# Elekid_03.net
KiCad netlist of a schematic drawn in Altium Designer
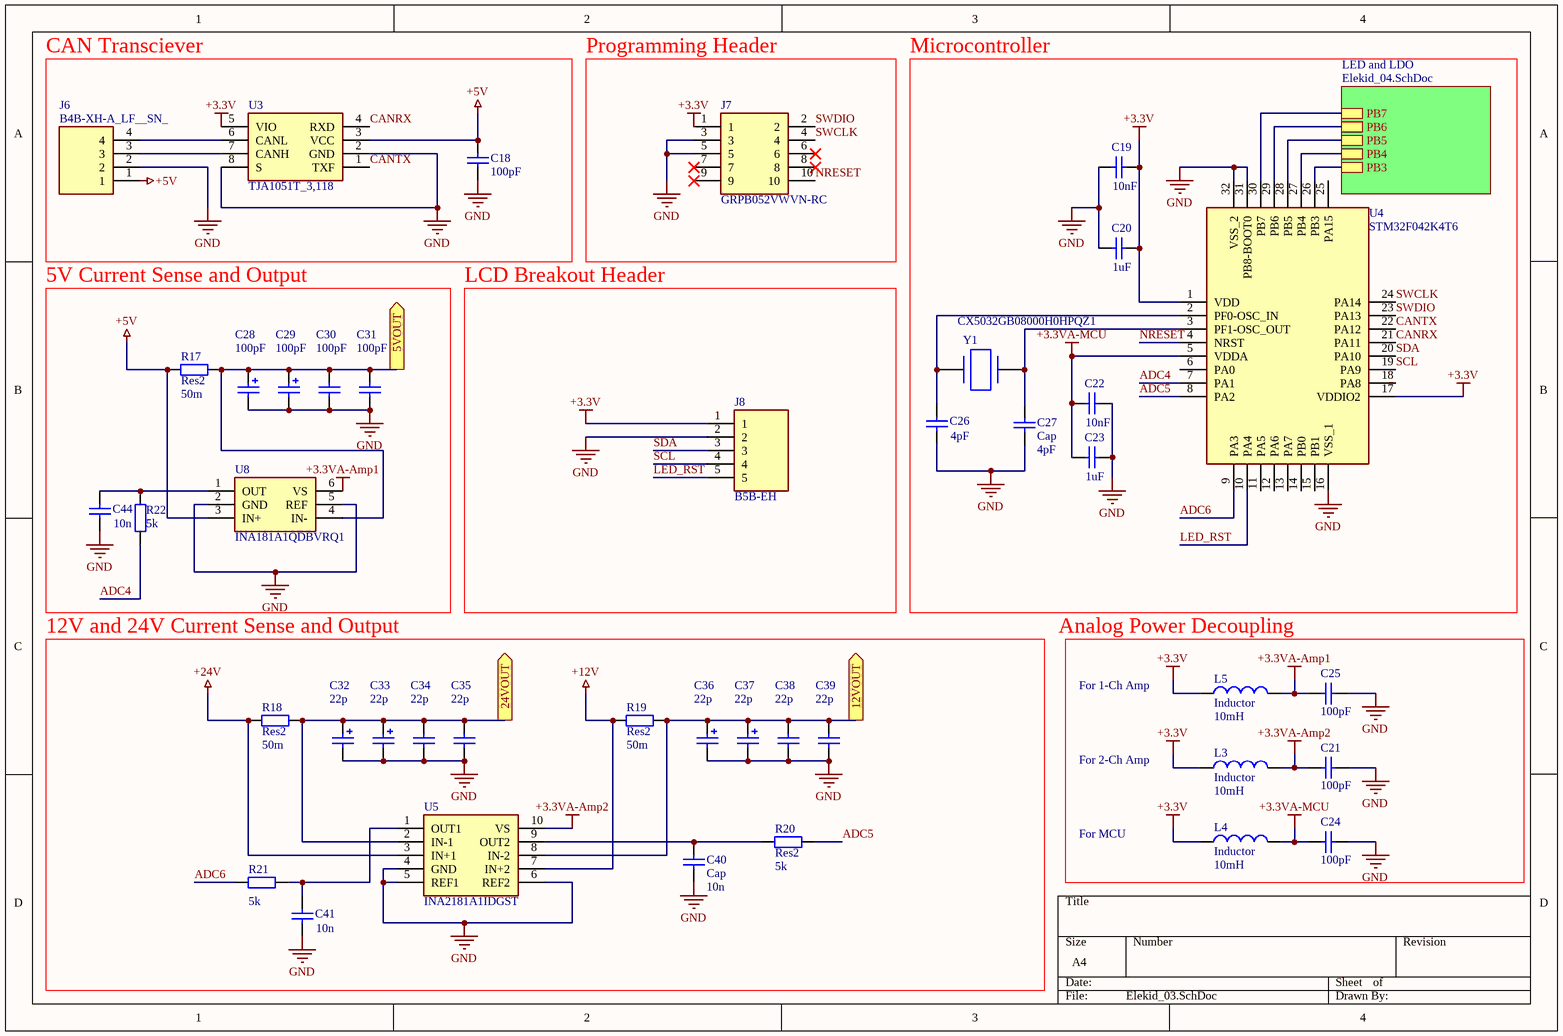
[diagram p0: Elekid_03.SchDoc]

(export (version "E")
  (design (tool "Eeschema 10.0.6"))
  (components
    (comp (ref "C18")
      (value "100pF")
      (footprint "C0805")
      (description "Capacitor")
      (fields (field (name "Comment") "Cap") (field (name "PUBLISHER") "Altium Limited"))
      (libsource (lib "Miscellaneous Devices") (part "Cap"))
    )
    (comp (ref "C19")
      (value "10nF")
      (footprint "C0805")
      (description "Capacitor")
      (fields (field (name "Comment") "Cap") (field (name "PUBLISHER") "Altium Limited"))
      (libsource (lib "Miscellaneous Devices") (part "Cap"))
    )
    (comp (ref "C20")
      (value "1uF")
      (footprint "C0805")
      (description "Capacitor")
      (fields (field (name "Comment") "Cap") (field (name "PUBLISHER") "Altium Limited"))
      (libsource (lib "Miscellaneous Devices") (part "Cap"))
    )
    (comp (ref "C21")
      (value "100pF")
      (footprint "C0805")
      (description "Capacitor")
      (fields (field (name "Comment") "Cap") (field (name "PUBLISHER") "Altium Limited"))
      (libsource (lib "Miscellaneous Devices") (part "Cap"))
    )
    (comp (ref "C22")
      (value "10nF")
      (footprint "C0805")
      (description "Capacitor")
      (fields (field (name "Comment") "Cap") (field (name "PUBLISHER") "Altium Limited"))
      (libsource (lib "Miscellaneous Devices") (part "Cap"))
    )
    (comp (ref "C23")
      (value "1uF")
      (footprint "C0805")
      (description "Capacitor")
      (fields (field (name "Comment") "Cap") (field (name "PUBLISHER") "Altium Limited"))
      (libsource (lib "Miscellaneous Devices") (part "Cap"))
    )
    (comp (ref "C24")
      (value "100pF")
      (footprint "C0805")
      (description "Capacitor")
      (fields (field (name "Comment") "Cap") (field (name "PUBLISHER") "Altium Limited"))
      (libsource (lib "Miscellaneous Devices") (part "Cap"))
    )
    (comp (ref "C25")
      (value "100pF")
      (footprint "C0805")
      (description "Capacitor")
      (fields (field (name "Comment") "Cap") (field (name "PUBLISHER") "Altium Limited"))
      (libsource (lib "Miscellaneous Devices") (part "Cap"))
    )
    (comp (ref "C26")
      (value "4pF")
      (footprint "C0805")
      (description "Capacitor")
      (fields (field (name "Comment") "Cap") (field (name "PUBLISHER") "Altium Limited"))
      (libsource (lib "Miscellaneous Devices") (part "Cap"))
    )
    (comp (ref "C27")
      (value "Cap")
      (footprint "C0805")
      (description "Capacitor")
      (fields (field (name "ALTIUM_VALUE") "4pF") (field (name "PUBLISHER") "Altium Limited"))
      (libsource (lib "Miscellaneous Devices") (part "Cap"))
    )
    (comp (ref "C28")
      (value "100pF")
      (footprint "C0805")
      (description "Polarized Capacitor (Axial)")
      (fields (field (name "Comment") "Cap Pol2") (field (name "PUBLISHER") "Altium Limited"))
      (libsource (lib "Miscellaneous Devices") (part "Cap Pol2"))
    )
    (comp (ref "C29")
      (value "100pF")
      (footprint "C0805")
      (description "Polarized Capacitor (Axial)")
      (fields (field (name "Comment") "Cap Pol2") (field (name "PUBLISHER") "Altium Limited"))
      (libsource (lib "Miscellaneous Devices") (part "Cap Pol2"))
    )
    (comp (ref "C30")
      (value "100pF")
      (footprint "C0805")
      (description "Capacitor")
      (fields (field (name "Comment") "Cap") (field (name "PUBLISHER") "Altium Limited"))
      (libsource (lib "Miscellaneous Devices") (part "Cap"))
    )
    (comp (ref "C31")
      (value "100pF")
      (footprint "C0805")
      (description "Capacitor")
      (fields (field (name "Comment") "Cap") (field (name "PUBLISHER") "Altium Limited"))
      (libsource (lib "Miscellaneous Devices") (part "Cap"))
    )
    (comp (ref "C32")
      (value "22p")
      (footprint "C0805")
      (description "Polarized Capacitor (Axial)")
      (fields (field (name "Comment") "Cap Pol2") (field (name "PUBLISHER") "Altium Limited"))
      (libsource (lib "Miscellaneous Devices") (part "Cap Pol2"))
    )
    (comp (ref "C33")
      (value "22p")
      (footprint "C0805")
      (description "Polarized Capacitor (Axial)")
      (fields (field (name "Comment") "Cap Pol2") (field (name "PUBLISHER") "Altium Limited"))
      (libsource (lib "Miscellaneous Devices") (part "Cap Pol2"))
    )
    (comp (ref "C34")
      (value "22p")
      (footprint "C0805")
      (description "Capacitor")
      (fields (field (name "Comment") "Cap") (field (name "PUBLISHER") "Altium Limited"))
      (libsource (lib "Miscellaneous Devices") (part "Cap"))
    )
    (comp (ref "C35")
      (value "22p")
      (footprint "C0805")
      (description "Capacitor")
      (fields (field (name "Comment") "Cap") (field (name "PUBLISHER") "Altium Limited"))
      (libsource (lib "Miscellaneous Devices") (part "Cap"))
    )
    (comp (ref "C36")
      (value "22p")
      (footprint "C0805")
      (description "Polarized Capacitor (Axial)")
      (fields (field (name "Comment") "Cap Pol2") (field (name "PUBLISHER") "Altium Limited"))
      (libsource (lib "Miscellaneous Devices") (part "Cap Pol2"))
    )
    (comp (ref "C37")
      (value "22p")
      (footprint "C0805")
      (description "Polarized Capacitor (Axial)")
      (fields (field (name "Comment") "Cap Pol2") (field (name "PUBLISHER") "Altium Limited"))
      (libsource (lib "Miscellaneous Devices") (part "Cap Pol2"))
    )
    (comp (ref "C38")
      (value "22p")
      (footprint "C0805")
      (description "Capacitor")
      (fields (field (name "Comment") "Cap") (field (name "PUBLISHER") "Altium Limited"))
      (libsource (lib "Miscellaneous Devices") (part "Cap"))
    )
    (comp (ref "C39")
      (value "22p")
      (footprint "C0805")
      (description "Capacitor")
      (fields (field (name "Comment") "Cap") (field (name "PUBLISHER") "Altium Limited"))
      (libsource (lib "Miscellaneous Devices") (part "Cap"))
    )
    (comp (ref "C40")
      (value "Cap")
      (footprint "C0805")
      (description "Capacitor")
      (fields (field (name "ALTIUM_VALUE") "10n") (field (name "PUBLISHER") "Altium Limited"))
      (libsource (lib "Miscellaneous Devices") (part "Cap"))
    )
    (comp (ref "C41")
      (value "10n")
      (footprint "C0805")
      (description "Capacitor")
      (fields (field (name "Comment") "Cap") (field (name "PUBLISHER") "Altium Limited"))
      (libsource (lib "Miscellaneous Devices") (part "Cap"))
    )
    (comp (ref "C44")
      (value "10n")
      (footprint "C0805")
      (description "Capacitor")
      (fields (field (name "Comment") "Cap") (field (name "PUBLISHER") "Altium Limited"))
      (libsource (lib "Miscellaneous Devices") (part "Cap"))
    )
    (comp (ref "J6")
      (value "B4B-XH-A_LF__SN_")
      (footprint "Embedded:B4BXHALFSN")
      (description "Connector")
      (fields (field (name "MANUFACTURER_PART_NUMBER") "B4B-XH-A(LF)(SN)"))
      (libsource (lib "*") (part "B4B-XH-A_LF__SN_"))
    )
    (comp (ref "J7")
      (value "GRPB052VWVN-RC")
      (footprint "Embedded:HDRV10W50P127_2X5_635X340X430P")
      (description "Connector")
      (libsource (lib "Embedded") (part "GRPB052VWVN-RC"))
    )
    (comp (ref "J8")
      (value "B5B-EH")
      (footprint "Embedded:SHDR5W64P0X250_1X5_1500X380X600P")
      (description "Connector")
      (libsource (lib "*") (part "B5B-EH"))
    )
    (comp (ref "L3")
      (value "Inductor")
      (footprint "c0805")
      (fields (field (name "ALTIUM_VALUE") "10mH") (field (name "PUBLISHER") "Altium Limited"))
      (libsource (lib "Miscellaneous Devices") (part "Inductor"))
    )
    (comp (ref "L4")
      (value "Inductor")
      (footprint "c0805")
      (fields (field (name "ALTIUM_VALUE") "10mH") (field (name "PUBLISHER") "Altium Limited"))
      (libsource (lib "Miscellaneous Devices") (part "Inductor"))
    )
    (comp (ref "L5")
      (value "Inductor")
      (footprint "c0805")
      (fields (field (name "ALTIUM_VALUE") "10mH") (field (name "PUBLISHER") "Altium Limited"))
      (libsource (lib "Miscellaneous Devices") (part "Inductor"))
    )
    (comp (ref "R17")
      (value "Res2")
      (footprint "C1206")
      (description "Resistor")
      (fields (field (name "ALTIUM_VALUE") "50m") (field (name "PUBLISHER") "Altium Limited"))
      (libsource (lib "Miscellaneous Devices") (part "Res2"))
    )
    (comp (ref "R18")
      (value "Res2")
      (footprint "C1206")
      (description "Resistor")
      (fields (field (name "ALTIUM_VALUE") "50m") (field (name "PUBLISHER") "Altium Limited"))
      (libsource (lib "Miscellaneous Devices") (part "Res2"))
    )
    (comp (ref "R19")
      (value "Res2")
      (footprint "C1206")
      (description "Resistor")
      (fields (field (name "ALTIUM_VALUE") "50m") (field (name "PUBLISHER") "Altium Limited"))
      (libsource (lib "Miscellaneous Devices") (part "Res2"))
    )
    (comp (ref "R20")
      (value "Res2")
      (footprint "C0805")
      (description "Resistor")
      (fields (field (name "ALTIUM_VALUE") "5k") (field (name "PUBLISHER") "Altium Limited"))
      (libsource (lib "Miscellaneous Devices") (part "Res2"))
    )
    (comp (ref "R21")
      (value "5k")
      (footprint "C0805")
      (description "Resistor")
      (fields (field (name "Comment") "Res2") (field (name "PUBLISHER") "Altium Limited"))
      (libsource (lib "Miscellaneous Devices") (part "Res2"))
    )
    (comp (ref "R22")
      (value "5k")
      (footprint "C0805")
      (description "Resistor")
      (fields (field (name "Comment") "Res2") (field (name "PUBLISHER") "Altium Limited"))
      (libsource (lib "") (part "Res2_1"))
    )
    (comp (ref "U3")
      (value "TJA1051T_3,118")
      (footprint "Embedded:SOIC127P600X175-8N")
      (description "Integrated Circuit")
      (fields
        (field (name "MANUFACTURER_PART_NUMBER") "TJA1051T/3,118")
        (field (name "MOUSER PART NUMBER") "771-TJA1051T3118")
      )
      (libsource (lib "Embedded") (part "TJA1051T_3,118"))
    )
    (comp (ref "U4")
      (value "STM32F042K4T6")
      (footprint "Embedded:QFP80P900X900X160-32N")
      (description "Integrated Circuit")
      (fields (field (name "MOUSER PART NUMBER") "511-STM32F042K4T6"))
      (libsource (lib "*") (part "STM32F042K4T6"))
    )
    (comp (ref "U5")
      (value "INA2181A1IDGST")
      (footprint "Embedded:SOP50P490X110-10N")
      (description "Integrated Circuit")
      (fields
        (field (name "MANUFACTURER_PART_NUMBER") "INA2181A4IDGST")
        (field (name "MOUSER PART NUMBER") "595-INA2181A4IDGST")
      )
      (libsource (lib "*") (part "INA2181A4IDGST"))
    )
    (comp (ref "U8")
      (value "INA181A1QDBVRQ1")
      (footprint "Embedded:SOT95P280X145-6N")
      (description "Integrated Circuit")
      (fields (field (name "MOUSER PART NUMBER") "595-INA181A1QDBVRQ1"))
      (libsource (lib "*") (part "INA181A1QDBVRQ1"))
    )
    (comp (ref "Y1")
      (value "CX5032GB08000H0HPQZ1")
      (footprint "Embedded:CX5032GB08000H0HPQZ1")
      (description "Crystal or Oscillator")
      (fields (field (name "MOUSER PART NUMBER") "581-CX532GB8HHPQZ1"))
      (libsource (lib "*") (part "CX5032GB08000H0HPQZ1"))
    )
  )
  (nets
    (net (code "1") (name "+3.3V") (class "Default")
      (node (ref "C19") (pin "1") (pinfunction "1_1") (pintype "passive"))
      (node (ref "C20") (pin "1") (pinfunction "1_1") (pintype "passive"))
      (node (ref "J7") (pin "1") (pinfunction "1_1") (pintype "passive"))
      (node (ref "J8") (pin "1") (pinfunction "1_1") (pintype "passive"))
      (node (ref "L3") (pin "1") (pinfunction "1_1") (pintype "passive"))
      (node (ref "L4") (pin "1") (pinfunction "1_1") (pintype "passive"))
      (node (ref "L5") (pin "1") (pinfunction "1_1") (pintype "passive"))
      (node (ref "U3") (pin "5") (pinfunction "VIO_5") (pintype "passive"))
      (node (ref "U4") (pin "1") (pinfunction "VDD_1") (pintype "passive"))
      (node (ref "U4") (pin "17") (pinfunction "VDDIO2_17") (pintype "passive"))
    )
    (net (code "2") (name "+3.3VA-Amp1") (class "Default")
      (node (ref "C25") (pin "1") (pinfunction "1_1") (pintype "passive"))
      (node (ref "L5") (pin "2") (pinfunction "2_2") (pintype "passive"))
      (node (ref "U8") (pin "6") (pinfunction "VS_6") (pintype "passive"))
    )
    (net (code "3") (name "+3.3VA-Amp2") (class "Default")
      (node (ref "C21") (pin "1") (pinfunction "1_1") (pintype "passive"))
      (node (ref "L3") (pin "2") (pinfunction "2_2") (pintype "passive"))
      (node (ref "U5") (pin "10") (pinfunction "VS_10") (pintype "passive"))
    )
    (net (code "4") (name "+3.3VA-MCU") (class "Default")
      (node (ref "C22") (pin "2") (pinfunction "2_2") (pintype "passive"))
      (node (ref "C23") (pin "2") (pinfunction "2_2") (pintype "passive"))
      (node (ref "C24") (pin "1") (pinfunction "1_1") (pintype "passive"))
      (node (ref "L4") (pin "2") (pinfunction "2_2") (pintype "passive"))
      (node (ref "U4") (pin "5") (pinfunction "VDDA_5") (pintype "passive"))
    )
    (net (code "5") (name "+5V") (class "Default")
      (node (ref "C18") (pin "2") (pinfunction "2_2") (pintype "passive"))
      (node (ref "J6") (pin "1") (pinfunction "1_1") (pintype "passive"))
      (node (ref "R17") (pin "1") (pinfunction "1_1") (pintype "passive"))
      (node (ref "U3") (pin "3") (pinfunction "VCC_3") (pintype "passive"))
      (node (ref "U8") (pin "3") (pinfunction "IN+_3") (pintype "passive"))
    )
    (net (code "6") (name "+12V") (class "Default")
      (node (ref "R19") (pin "1") (pinfunction "1_1") (pintype "passive"))
      (node (ref "U5") (pin "7") (pinfunction "IN+2_7") (pintype "passive"))
    )
    (net (code "7") (name "+24V") (class "Default")
      (node (ref "R18") (pin "1") (pinfunction "1_1") (pintype "passive"))
      (node (ref "U5") (pin "3") (pinfunction "IN+1_3") (pintype "passive"))
    )
    (net (code "8") (name "/5VOUT") (class "Default")
      (node (ref "C28") (pin "1") (pinfunction "1_1") (pintype "passive"))
      (node (ref "C29") (pin "1") (pinfunction "1_1") (pintype "passive"))
      (node (ref "C30") (pin "2") (pinfunction "2_2") (pintype "passive"))
      (node (ref "C31") (pin "2") (pinfunction "2_2") (pintype "passive"))
      (node (ref "R17") (pin "2") (pinfunction "2_2") (pintype "passive"))
      (node (ref "U8") (pin "4") (pinfunction "IN-_4") (pintype "passive"))
    )
    (net (code "9") (name "/12VOUT") (class "Default")
      (node (ref "C36") (pin "1") (pinfunction "1_1") (pintype "passive"))
      (node (ref "C37") (pin "1") (pinfunction "1_1") (pintype "passive"))
      (node (ref "C38") (pin "2") (pinfunction "2_2") (pintype "passive"))
      (node (ref "C39") (pin "2") (pinfunction "2_2") (pintype "passive"))
      (node (ref "R19") (pin "2") (pinfunction "2_2") (pintype "passive"))
      (node (ref "U5") (pin "8") (pinfunction "IN-2_8") (pintype "passive"))
    )
    (net (code "10") (name "/24VOUT") (class "Default")
      (node (ref "C32") (pin "1") (pinfunction "1_1") (pintype "passive"))
      (node (ref "C33") (pin "1") (pinfunction "1_1") (pintype "passive"))
      (node (ref "C34") (pin "2") (pinfunction "2_2") (pintype "passive"))
      (node (ref "C35") (pin "2") (pinfunction "2_2") (pintype "passive"))
      (node (ref "R18") (pin "2") (pinfunction "2_2") (pintype "passive"))
      (node (ref "U5") (pin "2") (pinfunction "IN-1_2") (pintype "passive"))
    )
    (net (code "11") (name "/ADC4") (class "Default")
      (node (ref "R22") (pin "1") (pinfunction "1_1") (pintype "passive"))
      (node (ref "U4") (pin "7") (pinfunction "PA1_7") (pintype "passive"))
    )
    (net (code "12") (name "/ADC5") (class "Default")
      (node (ref "R20") (pin "2") (pinfunction "2_2") (pintype "passive"))
      (node (ref "U4") (pin "8") (pinfunction "PA2_8") (pintype "passive"))
    )
    (net (code "13") (name "/ADC6") (class "Default")
      (node (ref "R21") (pin "1") (pinfunction "1_1") (pintype "passive"))
      (node (ref "U4") (pin "9") (pinfunction "PA3_9") (pintype "passive"))
    )
    (net (code "14") (name "/CANRX") (class "Default")
      (node (ref "U3") (pin "4") (pinfunction "RXD_4") (pintype "passive"))
      (node (ref "U4") (pin "21") (pinfunction "PA11_21") (pintype "passive"))
    )
    (net (code "15") (name "/CANTX") (class "Default")
      (node (ref "U3") (pin "1") (pinfunction "TXF_1") (pintype "passive"))
      (node (ref "U4") (pin "22") (pinfunction "PA12_22") (pintype "passive"))
    )
    (net (code "16") (name "/LED_RST") (class "Default")
      (node (ref "J8") (pin "5") (pinfunction "5_5") (pintype "passive"))
      (node (ref "U4") (pin "10") (pinfunction "PA4_10") (pintype "passive"))
    )
    (net (code "17") (name "/NRESET") (class "Default")
      (node (ref "J7") (pin "10") (pinfunction "10_10") (pintype "passive"))
      (node (ref "U4") (pin "4") (pinfunction "NRST_4") (pintype "passive"))
    )
    (net (code "18") (name "/PB3") (class "Default")
      (node (ref "U4") (pin "26") (pinfunction "PB3_26") (pintype "passive"))
    )
    (net (code "19") (name "/PB4") (class "Default")
      (node (ref "U4") (pin "27") (pinfunction "PB4_27") (pintype "passive"))
    )
    (net (code "20") (name "/PB5") (class "Default")
      (node (ref "U4") (pin "28") (pinfunction "PB5_28") (pintype "passive"))
    )
    (net (code "21") (name "/PB6") (class "Default")
      (node (ref "U4") (pin "29") (pinfunction "PB6_29") (pintype "passive"))
    )
    (net (code "22") (name "/PB7") (class "Default")
      (node (ref "U4") (pin "30") (pinfunction "PB7_30") (pintype "passive"))
    )
    (net (code "23") (name "/SCL") (class "Default")
      (node (ref "J8") (pin "4") (pinfunction "4_4") (pintype "passive"))
      (node (ref "U4") (pin "19") (pinfunction "PA9_19") (pintype "passive"))
    )
    (net (code "24") (name "/SDA") (class "Default")
      (node (ref "J8") (pin "3") (pinfunction "3_3") (pintype "passive"))
      (node (ref "U4") (pin "20") (pinfunction "PA10_20") (pintype "passive"))
    )
    (net (code "25") (name "/SWCLK") (class "Default")
      (node (ref "J7") (pin "4") (pinfunction "4_4") (pintype "passive"))
      (node (ref "U4") (pin "24") (pinfunction "PA14_24") (pintype "passive"))
    )
    (net (code "26") (name "/SWDIO") (class "Default")
      (node (ref "J7") (pin "2") (pinfunction "2_2") (pintype "passive"))
      (node (ref "U4") (pin "23") (pinfunction "PA13_23") (pintype "passive"))
    )
    (net (code "27") (name "GND") (class "Default")
      (node (ref "C18") (pin "1") (pinfunction "1_1") (pintype "passive"))
      (node (ref "C19") (pin "2") (pinfunction "2_2") (pintype "passive"))
      (node (ref "C20") (pin "2") (pinfunction "2_2") (pintype "passive"))
      (node (ref "C21") (pin "2") (pinfunction "2_2") (pintype "passive"))
      (node (ref "C22") (pin "1") (pinfunction "1_1") (pintype "passive"))
      (node (ref "C23") (pin "1") (pinfunction "1_1") (pintype "passive"))
      (node (ref "C24") (pin "2") (pinfunction "2_2") (pintype "passive"))
      (node (ref "C25") (pin "2") (pinfunction "2_2") (pintype "passive"))
      (node (ref "C26") (pin "1") (pinfunction "1_1") (pintype "passive"))
      (node (ref "C27") (pin "1") (pinfunction "1_1") (pintype "passive"))
      (node (ref "C28") (pin "2") (pinfunction "2_2") (pintype "passive"))
      (node (ref "C29") (pin "2") (pinfunction "2_2") (pintype "passive"))
      (node (ref "C30") (pin "1") (pinfunction "1_1") (pintype "passive"))
      (node (ref "C31") (pin "1") (pinfunction "1_1") (pintype "passive"))
      (node (ref "C32") (pin "2") (pinfunction "2_2") (pintype "passive"))
      (node (ref "C33") (pin "2") (pinfunction "2_2") (pintype "passive"))
      (node (ref "C34") (pin "1") (pinfunction "1_1") (pintype "passive"))
      (node (ref "C35") (pin "1") (pinfunction "1_1") (pintype "passive"))
      (node (ref "C36") (pin "2") (pinfunction "2_2") (pintype "passive"))
      (node (ref "C37") (pin "2") (pinfunction "2_2") (pintype "passive"))
      (node (ref "C38") (pin "1") (pinfunction "1_1") (pintype "passive"))
      (node (ref "C39") (pin "1") (pinfunction "1_1") (pintype "passive"))
      (node (ref "C40") (pin "1") (pinfunction "1_1") (pintype "passive"))
      (node (ref "C41") (pin "1") (pinfunction "1_1") (pintype "passive"))
      (node (ref "C44") (pin "1") (pinfunction "1_1") (pintype "passive"))
      (node (ref "J6") (pin "2") (pinfunction "2_2") (pintype "passive"))
      (node (ref "J7") (pin "3") (pinfunction "3_3") (pintype "passive"))
      (node (ref "J7") (pin "5") (pinfunction "5_5") (pintype "passive"))
      (node (ref "J8") (pin "2") (pinfunction "2_2") (pintype "passive"))
      (node (ref "U3") (pin "2") (pinfunction "GND_2") (pintype "passive"))
      (node (ref "U3") (pin "8") (pinfunction "S_8") (pintype "passive"))
      (node (ref "U4") (pin "16") (pinfunction "VSS_1_16") (pintype "passive"))
      (node (ref "U4") (pin "31") (pinfunction "PB8-BOOT0_31") (pintype "passive"))
      (node (ref "U4") (pin "32") (pinfunction "VSS_2_32") (pintype "passive"))
      (node (ref "U5") (pin "4") (pinfunction "GND_4") (pintype "passive"))
      (node (ref "U5") (pin "5") (pinfunction "REF1_5") (pintype "passive"))
      (node (ref "U5") (pin "6") (pinfunction "REF2_6") (pintype "passive"))
      (node (ref "U8") (pin "2") (pinfunction "GND_2") (pintype "passive"))
      (node (ref "U8") (pin "5") (pinfunction "REF_5") (pintype "passive"))
    )
    (net (code "28") (name "Net-(U3-CANH)") (class "Default")
      (node (ref "J6") (pin "3") (pinfunction "3_3") (pintype "passive"))
      (node (ref "U3") (pin "7") (pinfunction "CANH_7") (pintype "passive"))
    )
    (net (code "29") (name "Net-(U3-CANL)") (class "Default")
      (node (ref "J6") (pin "4") (pinfunction "4_4") (pintype "passive"))
      (node (ref "U3") (pin "6") (pinfunction "CANL_6") (pintype "passive"))
    )
    (net (code "30") (name "Net-(U4-PF0-OSC_IN)") (class "Default")
      (node (ref "C26") (pin "2") (pinfunction "2_2") (pintype "passive"))
      (node (ref "U4") (pin "2") (pinfunction "PF0-OSC_IN_2") (pintype "passive"))
      (node (ref "Y1") (pin "2") (pinfunction "2_2") (pintype "passive"))
    )
    (net (code "31") (name "Net-(U4-PF1-OSC_OUT)") (class "Default")
      (node (ref "C27") (pin "2") (pinfunction "2_2") (pintype "passive"))
      (node (ref "U4") (pin "3") (pinfunction "PF1-OSC_OUT_3") (pintype "passive"))
      (node (ref "Y1") (pin "1") (pinfunction "1_1") (pintype "passive"))
    )
    (net (code "32") (name "Net-(U5-OUT1)") (class "Default")
      (node (ref "C41") (pin "2") (pinfunction "2_2") (pintype "passive"))
      (node (ref "R21") (pin "2") (pinfunction "2_2") (pintype "passive"))
      (node (ref "U5") (pin "1") (pinfunction "OUT1_1") (pintype "passive"))
    )
    (net (code "33") (name "Net-(U5-OUT2)") (class "Default")
      (node (ref "C40") (pin "2") (pinfunction "2_2") (pintype "passive"))
      (node (ref "R20") (pin "1") (pinfunction "1_1") (pintype "passive"))
      (node (ref "U5") (pin "9") (pinfunction "OUT2_9") (pintype "passive"))
    )
    (net (code "34") (name "Net-(U8-OUT)") (class "Default")
      (node (ref "C44") (pin "2") (pinfunction "2_2") (pintype "passive"))
      (node (ref "R22") (pin "2") (pinfunction "2_2") (pintype "passive"))
      (node (ref "U8") (pin "1") (pinfunction "OUT_1") (pintype "passive"))
    )
    (net (code "35") (name "unconnected-(J7-Pad6)") (class "Default")
      (node (ref "J7") (pin "6") (pinfunction "6_6") (pintype "passive+no_connect"))
    )
    (net (code "36") (name "unconnected-(J7-Pad7)") (class "Default")
      (node (ref "J7") (pin "7") (pinfunction "7_7") (pintype "passive+no_connect"))
    )
    (net (code "37") (name "unconnected-(J7-Pad8)") (class "Default")
      (node (ref "J7") (pin "8") (pinfunction "8_8") (pintype "passive+no_connect"))
    )
    (net (code "38") (name "unconnected-(J7-Pad9)") (class "Default")
      (node (ref "J7") (pin "9") (pinfunction "9_9") (pintype "passive+no_connect"))
    )
    (net (code "39") (name "unconnected-(U4-PA0-Pad6)") (class "Default")
      (node (ref "U4") (pin "6") (pinfunction "PA0_6") (pintype "passive"))
    )
    (net (code "40") (name "unconnected-(U4-PA5-Pad11)") (class "Default")
      (node (ref "U4") (pin "11") (pinfunction "PA5_11") (pintype "passive"))
    )
    (net (code "41") (name "unconnected-(U4-PA6-Pad12)") (class "Default")
      (node (ref "U4") (pin "12") (pinfunction "PA6_12") (pintype "passive"))
    )
    (net (code "42") (name "unconnected-(U4-PA7-Pad13)") (class "Default")
      (node (ref "U4") (pin "13") (pinfunction "PA7_13") (pintype "passive"))
    )
    (net (code "43") (name "unconnected-(U4-PA8-Pad18)") (class "Default")
      (node (ref "U4") (pin "18") (pinfunction "PA8_18") (pintype "passive"))
    )
    (net (code "44") (name "unconnected-(U4-PA15-Pad25)") (class "Default")
      (node (ref "U4") (pin "25") (pinfunction "PA15_25") (pintype "passive"))
    )
    (net (code "45") (name "unconnected-(U4-PB0-Pad14)") (class "Default")
      (node (ref "U4") (pin "14") (pinfunction "PB0_14") (pintype "passive"))
    )
    (net (code "46") (name "unconnected-(U4-PB1-Pad15)") (class "Default")
      (node (ref "U4") (pin "15") (pinfunction "PB1_15") (pintype "passive"))
    )
  )
)
